# Sheet1.net
KiCad netlist of a schematic drawn in Altium Designer
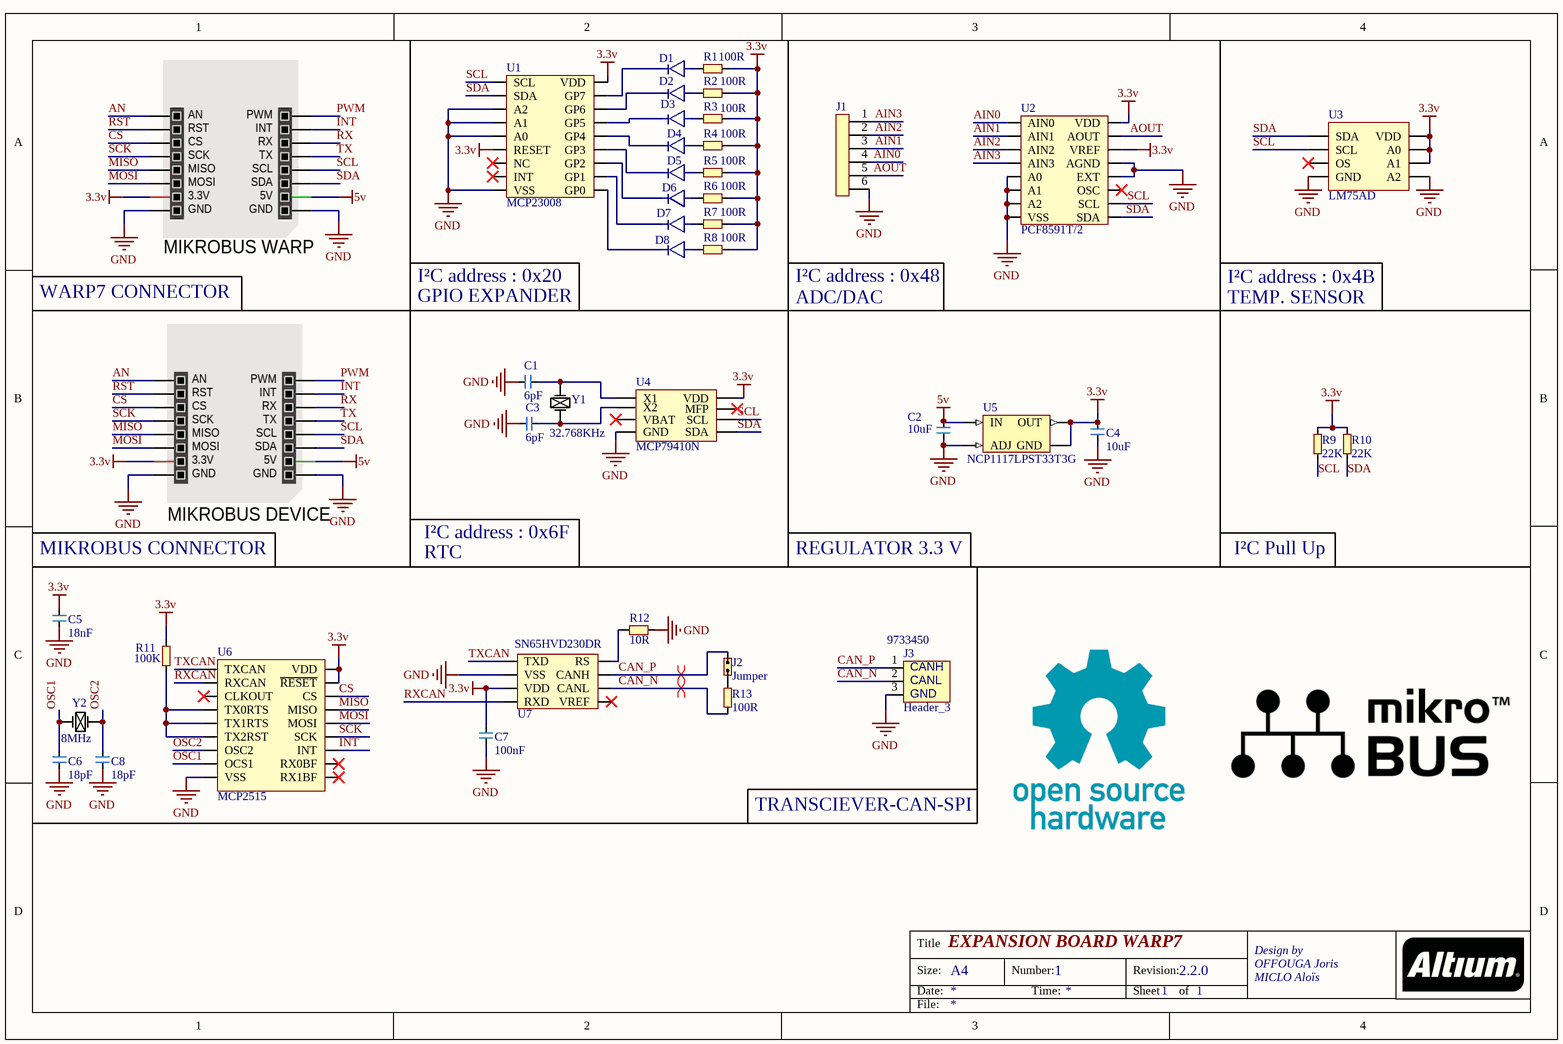
[diagram p0: Sheet1.SchDoc]

(export (version "E")
  (design (tool "Eeschema 10.0.6"))
  (components
    (comp (ref "C1")
      (value "6pF")
      (footprint "0805")
      (description "Condensateur")
      (libsource (lib "Schlib1") (part "Condensateur"))
    )
    (comp (ref "C2")
      (value "10uF")
      (footprint "0805")
      (description "Condensateur")
      (libsource (lib "Schlib1") (part "Condensateur"))
    )
    (comp (ref "C3")
      (value "6pF")
      (footprint "0805")
      (description "Condensateur")
      (libsource (lib "Schlib1") (part "Condensateur"))
    )
    (comp (ref "C4")
      (value "10uF")
      (footprint "0805")
      (description "Condensateur")
      (libsource (lib "Schlib1") (part "Condensateur"))
    )
    (comp (ref "C5")
      (value "18nF")
      (footprint "0805")
      (description "Condensateur")
      (libsource (lib "Schlib1") (part "Condensateur"))
    )
    (comp (ref "C6")
      (value "18pF")
      (footprint "0805")
      (description "Condensateur")
      (libsource (lib "Schlib1") (part "Condensateur"))
    )
    (comp (ref "C7")
      (value "100nF")
      (footprint "0805")
      (description "Condensateur")
      (libsource (lib "Schlib1") (part "Condensateur"))
    )
    (comp (ref "C8")
      (value "18pF")
      (footprint "0805")
      (description "Condensateur")
      (libsource (lib "Schlib1") (part "Condensateur"))
    )
    (comp (ref "D1")
      (value "Diode")
      (footprint "led")
      (description "led")
      (libsource (lib "Schlib1") (part "Diode"))
    )
    (comp (ref "D2")
      (value "Diode")
      (footprint "led")
      (description "led")
      (libsource (lib "Schlib1") (part "Diode"))
    )
    (comp (ref "D3")
      (value "Diode")
      (footprint "led")
      (description "led")
      (libsource (lib "Schlib1") (part "Diode"))
    )
    (comp (ref "D4")
      (value "Diode")
      (footprint "led")
      (description "led")
      (libsource (lib "Schlib1") (part "Diode"))
    )
    (comp (ref "D5")
      (value "Diode")
      (footprint "led")
      (description "led")
      (libsource (lib "Schlib1") (part "Diode"))
    )
    (comp (ref "D6")
      (value "Diode")
      (footprint "led")
      (description "led")
      (libsource (lib "Schlib1") (part "Diode"))
    )
    (comp (ref "D7")
      (value "Diode")
      (footprint "led")
      (description "led")
      (libsource (lib "Schlib1") (part "Diode"))
    )
    (comp (ref "D8")
      (value "Diode")
      (footprint "led")
      (description "led")
      (libsource (lib "Schlib1") (part "Diode"))
    )
    (comp (ref "J1") (value "Header_6") (footprint "Header 6") (libsource (lib "Schlib1") (part "Header_6")))
    (comp (ref "J2") (value "Jumper") (footprint "Header 2") (libsource (lib "Schlib1") (part "Jumper")))
    (comp (ref "J3")
      (value "Header_3")
      (footprint "Header 3")
      (fields (field (name "SUPPLIER PART NUMBER 1") "9733450"))
      (libsource (lib "Schlib1") (part "Header_3"))
    )
    (comp (ref "MIKROBUS DEVICE")
      (value "MIKROBUS HOST CONN.")
      (footprint "MIKROBUS HOST CONN.")
      (description "mikroBUS Host Socket")
      (libsource (lib "altium-import") (part "root_0_MIKROBUS HOST CONN._1_"))
    )
    (comp (ref "MIKROBUS WARP")
      (value "MIKROBUS HOST CONN.")
      (footprint "MIKROBUS WARP CONN.")
      (description "mikroBUS Host Socket")
      (libsource (lib "altium-import") (part "root_0_MIKROBUS HOST CONN._1_"))
    )
    (comp (ref "R1") (value "100R") (footprint "0805") (libsource (lib "") (part "Resistance_1")))
    (comp (ref "R2") (value "100R") (footprint "0805") (libsource (lib "") (part "Resistance_1")))
    (comp (ref "R3") (value "100R") (footprint "0805") (libsource (lib "") (part "Resistance_1")))
    (comp (ref "R4") (value "100R") (footprint "0805") (libsource (lib "") (part "Resistance_1")))
    (comp (ref "R5") (value "100R") (footprint "0805") (libsource (lib "") (part "Resistance_1")))
    (comp (ref "R6") (value "100R") (footprint "0805") (libsource (lib "") (part "Resistance_1")))
    (comp (ref "R7") (value "100R") (footprint "0805") (libsource (lib "") (part "Resistance_1")))
    (comp (ref "R8") (value "100R") (footprint "0805") (libsource (lib "") (part "Resistance_1")))
    (comp (ref "R9") (value "22K") (footprint "0805") (libsource (lib "Schlib1") (part "Resistance")))
    (comp (ref "R10") (value "22K") (footprint "0805") (libsource (lib "Schlib1") (part "Resistance")))
    (comp (ref "R11") (value "100K") (footprint "0805") (libsource (lib "Schlib1") (part "Resistance")))
    (comp (ref "R12") (value "10R") (footprint "0805") (libsource (lib "") (part "Resistance_2")))
    (comp (ref "R13") (value "100R") (footprint "0805") (libsource (lib "Schlib1") (part "Resistance")))
    (comp (ref "U1") (value "MCP23008") (footprint "SOIC 18") (libsource (lib "Schlib1") (part "MCP23008")))
    (comp (ref "U2")
      (value "PCF8591T/2")
      (footprint "SOIC 16")
      (libsource (lib "Schlib1") (part "PCF8591T/2"))
    )
    (comp (ref "U3") (value "LM75AD") (footprint "SOIC 8") (libsource (lib "Schlib1") (part "LM75AD")))
    (comp (ref "U4") (value "MCP79410N") (footprint "SOIC 8") (libsource (lib "Schlib1") (part "MCP7940N")))
    (comp (ref "U5")
      (value "NCP1117LPST33T3G")
      (footprint "SOT-223")
      (libsource (lib "Schlib1") (part "NCP1117LPST33T3G"))
    )
    (comp (ref "U6") (value "MCP2515") (footprint "SOIC 18") (libsource (lib "Schlib1") (part "MCP2515")))
    (comp (ref "U7")
      (value "SN65HVD230DR")
      (footprint "SOIC 8")
      (libsource (lib "altium-import") (part "root_0_SN65HVD230DR_"))
    )
    (comp (ref "Y1") (value "32.768KHz") (footprint "ABS-07") (libsource (lib "") (part "Quartz_1")))
    (comp (ref "Y2")
      (value "8MHz")
      (footprint "QUARTZ_CMS_6.2x3.7")
      (libsource (lib "Schlib1") (part "Quartz"))
    )
  )
  (nets
    (net (code "1") (name "/AIN0") (class "Default")
      (node (ref "J1") (pin "4") (pinfunction "4_4") (pintype "passive"))
      (node (ref "U2") (pin "1") (pinfunction "AIN0_1") (pintype "passive"))
    )
    (net (code "2") (name "/AIN1") (class "Default")
      (node (ref "J1") (pin "3") (pinfunction "3_3") (pintype "passive"))
      (node (ref "U2") (pin "2") (pinfunction "AIN1_2") (pintype "passive"))
    )
    (net (code "3") (name "/AIN2") (class "Default")
      (node (ref "J1") (pin "2") (pinfunction "2_2") (pintype "passive"))
      (node (ref "U2") (pin "3") (pinfunction "AIN2_3") (pintype "passive"))
    )
    (net (code "4") (name "/AIN3") (class "Default")
      (node (ref "J1") (pin "1") (pinfunction "1_1") (pintype "passive"))
      (node (ref "U2") (pin "4") (pinfunction "AIN3_4") (pintype "passive"))
    )
    (net (code "5") (name "/AN") (class "Default")
      (node (ref "MIKROBUS DEVICE") (pin "1") (pinfunction "AN_1") (pintype "passive"))
      (node (ref "MIKROBUS WARP") (pin "1") (pinfunction "AN_1") (pintype "passive"))
    )
    (net (code "6") (name "/AOUT") (class "Default")
      (node (ref "J1") (pin "5") (pinfunction "5_5") (pintype "passive"))
      (node (ref "U2") (pin "15") (pinfunction "AOUT_15") (pintype "passive"))
    )
    (net (code "7") (name "/CAN_N") (class "Default")
      (node (ref "J3") (pin "2") (pinfunction "2_2") (pintype "passive"))
      (node (ref "R13") (pin "1") (pinfunction "1_1") (pintype "passive"))
      (node (ref "U7") (pin "6") (pinfunction "CANL_6") (pintype "passive"))
    )
    (net (code "8") (name "/CAN_P") (class "Default")
      (node (ref "J2") (pin "1") (pinfunction "1_1") (pintype "passive"))
      (node (ref "J3") (pin "1") (pinfunction "1_1") (pintype "passive"))
      (node (ref "U7") (pin "7") (pinfunction "CANH_7") (pintype "passive"))
    )
    (net (code "9") (name "/CS") (class "Default")
      (node (ref "MIKROBUS DEVICE") (pin "3") (pinfunction "CS_3") (pintype "passive"))
      (node (ref "MIKROBUS WARP") (pin "3") (pinfunction "CS_3") (pintype "passive"))
      (node (ref "U6") (pin "16") (pinfunction "CS_16") (pintype "passive"))
    )
    (net (code "10") (name "/INT") (class "Default")
      (node (ref "MIKROBUS DEVICE") (pin "15") (pinfunction "INT_15") (pintype "passive"))
      (node (ref "MIKROBUS WARP") (pin "15") (pinfunction "INT_15") (pintype "passive"))
      (node (ref "U6") (pin "12") (pinfunction "INT_12") (pintype "passive"))
    )
    (net (code "11") (name "/MISO") (class "Default")
      (node (ref "MIKROBUS DEVICE") (pin "5") (pinfunction "MISO_5") (pintype "passive"))
      (node (ref "MIKROBUS WARP") (pin "5") (pinfunction "MISO_5") (pintype "passive"))
      (node (ref "U6") (pin "15") (pinfunction "MISO_15") (pintype "passive"))
    )
    (net (code "12") (name "/MOSI") (class "Default")
      (node (ref "MIKROBUS DEVICE") (pin "6") (pinfunction "MOSI_6") (pintype "passive"))
      (node (ref "MIKROBUS WARP") (pin "6") (pinfunction "MOSI_6") (pintype "passive"))
      (node (ref "U6") (pin "14") (pinfunction "MOSI_14") (pintype "passive"))
    )
    (net (code "13") (name "/OSC1") (class "Default")
      (node (ref "C6") (pin "2") (pinfunction "2_2") (pintype "passive"))
      (node (ref "U6") (pin "8") (pinfunction "OCS1_8") (pintype "passive"))
      (node (ref "Y2") (pin "1") (pinfunction "1_1") (pintype "passive"))
    )
    (net (code "14") (name "/OSC2") (class "Default")
      (node (ref "C8") (pin "2") (pinfunction "2_2") (pintype "passive"))
      (node (ref "U6") (pin "7") (pinfunction "OSC2_7") (pintype "passive"))
      (node (ref "Y2") (pin "2") (pinfunction "2_2") (pintype "passive"))
    )
    (net (code "15") (name "/PWM") (class "Default")
      (node (ref "MIKROBUS DEVICE") (pin "16") (pinfunction "PWM_16") (pintype "passive"))
      (node (ref "MIKROBUS WARP") (pin "16") (pinfunction "PWM_16") (pintype "passive"))
    )
    (net (code "16") (name "/RST") (class "Default")
      (node (ref "MIKROBUS DEVICE") (pin "2") (pinfunction "RST_2") (pintype "passive"))
      (node (ref "MIKROBUS WARP") (pin "2") (pinfunction "RST_2") (pintype "passive"))
    )
    (net (code "17") (name "/RX") (class "Default")
      (node (ref "MIKROBUS DEVICE") (pin "14") (pinfunction "RX_14") (pintype "passive"))
      (node (ref "MIKROBUS WARP") (pin "14") (pinfunction "RX_14") (pintype "passive"))
    )
    (net (code "18") (name "/RXCAN") (class "Default")
      (node (ref "U6") (pin "2") (pinfunction "RXCAN_2") (pintype "passive"))
      (node (ref "U7") (pin "4") (pinfunction "RXD_4") (pintype "passive"))
    )
    (net (code "19") (name "/SCK") (class "Default")
      (node (ref "MIKROBUS DEVICE") (pin "4") (pinfunction "SCK_4") (pintype "passive"))
      (node (ref "MIKROBUS WARP") (pin "4") (pinfunction "SCK_4") (pintype "passive"))
      (node (ref "U6") (pin "13") (pinfunction "SCK_13") (pintype "passive"))
    )
    (net (code "20") (name "/SCL") (class "Default")
      (node (ref "MIKROBUS DEVICE") (pin "12") (pinfunction "SCL_12") (pintype "passive"))
      (node (ref "MIKROBUS WARP") (pin "12") (pinfunction "SCL_12") (pintype "passive"))
      (node (ref "R9") (pin "1") (pinfunction "1_1") (pintype "passive"))
      (node (ref "U1") (pin "1") (pinfunction "SCL_1") (pintype "passive"))
      (node (ref "U2") (pin "10") (pinfunction "SCL_10") (pintype "passive"))
      (node (ref "U3") (pin "2") (pinfunction "SCL_2") (pintype "passive"))
      (node (ref "U4") (pin "6") (pinfunction "SCL_6") (pintype "passive"))
    )
    (net (code "21") (name "/SDA") (class "Default")
      (node (ref "MIKROBUS DEVICE") (pin "11") (pinfunction "SDA_11") (pintype "passive"))
      (node (ref "MIKROBUS WARP") (pin "11") (pinfunction "SDA_11") (pintype "passive"))
      (node (ref "R10") (pin "1") (pinfunction "1_1") (pintype "passive"))
      (node (ref "U1") (pin "2") (pinfunction "SDA_2") (pintype "passive"))
      (node (ref "U2") (pin "9") (pinfunction "SDA_9") (pintype "passive"))
      (node (ref "U3") (pin "1") (pinfunction "SDA_1") (pintype "passive"))
      (node (ref "U4") (pin "5") (pinfunction "SDA_5") (pintype "passive"))
    )
    (net (code "22") (name "/TX") (class "Default")
      (node (ref "MIKROBUS DEVICE") (pin "13") (pinfunction "TX_13") (pintype "passive"))
      (node (ref "MIKROBUS WARP") (pin "13") (pinfunction "TX_13") (pintype "passive"))
    )
    (net (code "23") (name "/TXCAN") (class "Default")
      (node (ref "U6") (pin "1") (pinfunction "TXCAN_1") (pintype "passive"))
      (node (ref "U7") (pin "1") (pinfunction "TXD_1") (pintype "passive"))
    )
    (net (code "24") (name "3.3v") (class "Default")
      (node (ref "C4") (pin "1") (pinfunction "1_1") (pintype "passive"))
      (node (ref "C5") (pin "1") (pinfunction "1_1") (pintype "passive"))
      (node (ref "C7") (pin "2") (pinfunction "2_2") (pintype "passive"))
      (node (ref "MIKROBUS DEVICE") (pin "7") (pinfunction "3.3V_7") (pintype "passive"))
      (node (ref "MIKROBUS WARP") (pin "7") (pinfunction "3.3V_7") (pintype "passive"))
      (node (ref "R1") (pin "2") (pinfunction "2_2") (pintype "passive"))
      (node (ref "R10") (pin "2") (pinfunction "2_2") (pintype "passive"))
      (node (ref "R11") (pin "2") (pinfunction "2_2") (pintype "passive"))
      (node (ref "R2") (pin "2") (pinfunction "2_2") (pintype "passive"))
      (node (ref "R3") (pin "2") (pinfunction "2_2") (pintype "passive"))
      (node (ref "R4") (pin "2") (pinfunction "2_2") (pintype "passive"))
      (node (ref "R5") (pin "2") (pinfunction "2_2") (pintype "passive"))
      (node (ref "R6") (pin "2") (pinfunction "2_2") (pintype "passive"))
      (node (ref "R7") (pin "2") (pinfunction "2_2") (pintype "passive"))
      (node (ref "R8") (pin "2") (pinfunction "2_2") (pintype "passive"))
      (node (ref "R9") (pin "2") (pinfunction "2_2") (pintype "passive"))
      (node (ref "U1") (pin "18") (pinfunction "VDD_18") (pintype "passive"))
      (node (ref "U1") (pin "6") (pinfunction "RESET_6") (pintype "passive"))
      (node (ref "U2") (pin "14") (pinfunction "VREF_14") (pintype "passive"))
      (node (ref "U2") (pin "16") (pinfunction "VDD_16") (pintype "passive"))
      (node (ref "U3") (pin "6") (pinfunction "A1_6") (pintype "passive"))
      (node (ref "U3") (pin "7") (pinfunction "A0_7") (pintype "passive"))
      (node (ref "U3") (pin "8") (pinfunction "VDD_8") (pintype "passive"))
      (node (ref "U4") (pin "8") (pinfunction "VDD_8") (pintype "passive"))
      (node (ref "U5") (pin "2") (pinfunction "OUT_2") (pintype "output"))
      (node (ref "U5") (pin "4") (pinfunction "GND_4") (pintype "passive"))
      (node (ref "U6") (pin "17") (pinfunction "~{RESET}_17") (pintype "passive"))
      (node (ref "U6") (pin "18") (pinfunction "VDD_18") (pintype "passive"))
      (node (ref "U7") (pin "3") (pinfunction "VDD_3") (pintype "passive"))
    )
    (net (code "25") (name "5v") (class "Default")
      (node (ref "C2") (pin "1") (pinfunction "1_1") (pintype "passive"))
      (node (ref "MIKROBUS DEVICE") (pin "10") (pinfunction "5V_10") (pintype "passive"))
      (node (ref "MIKROBUS WARP") (pin "10") (pinfunction "5V_10") (pintype "passive"))
      (node (ref "U5") (pin "3") (pinfunction "IN_3") (pintype "input"))
    )
    (net (code "26") (name "GND") (class "Default")
      (node (ref "C1") (pin "2") (pinfunction "2_2") (pintype "passive"))
      (node (ref "C2") (pin "2") (pinfunction "2_2") (pintype "passive"))
      (node (ref "C3") (pin "2") (pinfunction "2_2") (pintype "passive"))
      (node (ref "C4") (pin "2") (pinfunction "2_2") (pintype "passive"))
      (node (ref "C5") (pin "2") (pinfunction "2_2") (pintype "passive"))
      (node (ref "C6") (pin "1") (pinfunction "1_1") (pintype "passive"))
      (node (ref "C7") (pin "1") (pinfunction "1_1") (pintype "passive"))
      (node (ref "C8") (pin "1") (pinfunction "1_1") (pintype "passive"))
      (node (ref "J1") (pin "6") (pinfunction "6_6") (pintype "passive"))
      (node (ref "J3") (pin "3") (pinfunction "3_3") (pintype "passive"))
      (node (ref "MIKROBUS DEVICE") (pin "8") (pinfunction "GND_8") (pintype "passive"))
      (node (ref "MIKROBUS DEVICE") (pin "9") (pinfunction "GND_9") (pintype "passive"))
      (node (ref "MIKROBUS WARP") (pin "8") (pinfunction "GND_8") (pintype "passive"))
      (node (ref "MIKROBUS WARP") (pin "9") (pinfunction "GND_9") (pintype "passive"))
      (node (ref "R12") (pin "1") (pinfunction "1_1") (pintype "passive"))
      (node (ref "U1") (pin "3") (pinfunction "A2_3") (pintype "passive"))
      (node (ref "U1") (pin "4") (pinfunction "A1_4") (pintype "passive"))
      (node (ref "U1") (pin "5") (pinfunction "A0_5") (pintype "passive"))
      (node (ref "U1") (pin "9") (pinfunction "VSS_9") (pintype "passive"))
      (node (ref "U2") (pin "12") (pinfunction "EXT_12") (pintype "passive"))
      (node (ref "U2") (pin "13") (pinfunction "AGND_13") (pintype "passive"))
      (node (ref "U2") (pin "5") (pinfunction "A0_5") (pintype "passive"))
      (node (ref "U2") (pin "6") (pinfunction "A1_6") (pintype "passive"))
      (node (ref "U2") (pin "7") (pinfunction "A2_7") (pintype "passive"))
      (node (ref "U2") (pin "8") (pinfunction "VSS_8") (pintype "passive"))
      (node (ref "U3") (pin "4") (pinfunction "GND_4") (pintype "passive"))
      (node (ref "U3") (pin "5") (pinfunction "A2_5") (pintype "passive"))
      (node (ref "U4") (pin "4") (pinfunction "GND_4") (pintype "passive"))
      (node (ref "U5") (pin "1") (pinfunction "ADJ_1") (pintype "input"))
      (node (ref "U6") (pin "9") (pinfunction "VSS_9") (pintype "passive"))
      (node (ref "U7") (pin "2") (pinfunction "VSS_2") (pintype "passive"))
    )
    (net (code "27") (name "Net-(D1-Pad1)") (class "Default")
      (node (ref "D1") (pin "1") (pinfunction "1_1") (pintype "passive"))
      (node (ref "R1") (pin "1") (pinfunction "1_1") (pintype "passive"))
    )
    (net (code "28") (name "Net-(D2-Pad1)") (class "Default")
      (node (ref "D2") (pin "1") (pinfunction "1_1") (pintype "passive"))
      (node (ref "R2") (pin "1") (pinfunction "1_1") (pintype "passive"))
    )
    (net (code "29") (name "Net-(D3-Pad1)") (class "Default")
      (node (ref "D3") (pin "1") (pinfunction "1_1") (pintype "passive"))
      (node (ref "R3") (pin "1") (pinfunction "1_1") (pintype "passive"))
    )
    (net (code "30") (name "Net-(D4-Pad1)") (class "Default")
      (node (ref "D4") (pin "1") (pinfunction "1_1") (pintype "passive"))
      (node (ref "R4") (pin "1") (pinfunction "1_1") (pintype "passive"))
    )
    (net (code "31") (name "Net-(D5-Pad1)") (class "Default")
      (node (ref "D5") (pin "1") (pinfunction "1_1") (pintype "passive"))
      (node (ref "R5") (pin "1") (pinfunction "1_1") (pintype "passive"))
    )
    (net (code "32") (name "Net-(D6-Pad1)") (class "Default")
      (node (ref "D6") (pin "1") (pinfunction "1_1") (pintype "passive"))
      (node (ref "R6") (pin "1") (pinfunction "1_1") (pintype "passive"))
    )
    (net (code "33") (name "Net-(D7-Pad1)") (class "Default")
      (node (ref "D7") (pin "1") (pinfunction "1_1") (pintype "passive"))
      (node (ref "R7") (pin "1") (pinfunction "1_1") (pintype "passive"))
    )
    (net (code "34") (name "Net-(D8-Pad1)") (class "Default")
      (node (ref "D8") (pin "1") (pinfunction "1_1") (pintype "passive"))
      (node (ref "R8") (pin "1") (pinfunction "1_1") (pintype "passive"))
    )
    (net (code "35") (name "Net-(J2-Pad2)") (class "Default")
      (node (ref "J2") (pin "2") (pinfunction "2_2") (pintype "passive"))
      (node (ref "R13") (pin "2") (pinfunction "2_2") (pintype "passive"))
    )
    (net (code "36") (name "Net-(U1-GP0)") (class "Default")
      (node (ref "D8") (pin "2") (pinfunction "2_2") (pintype "passive"))
      (node (ref "U1") (pin "10") (pinfunction "GP0_10") (pintype "passive"))
    )
    (net (code "37") (name "Net-(U1-GP1)") (class "Default")
      (node (ref "D7") (pin "2") (pinfunction "2_2") (pintype "passive"))
      (node (ref "U1") (pin "11") (pinfunction "GP1_11") (pintype "passive"))
    )
    (net (code "38") (name "Net-(U1-GP2)") (class "Default")
      (node (ref "D6") (pin "2") (pinfunction "2_2") (pintype "passive"))
      (node (ref "U1") (pin "12") (pinfunction "GP2_12") (pintype "passive"))
    )
    (net (code "39") (name "Net-(U1-GP3)") (class "Default")
      (node (ref "D5") (pin "2") (pinfunction "2_2") (pintype "passive"))
      (node (ref "U1") (pin "13") (pinfunction "GP3_13") (pintype "passive"))
    )
    (net (code "40") (name "Net-(U1-GP4)") (class "Default")
      (node (ref "D4") (pin "2") (pinfunction "2_2") (pintype "passive"))
      (node (ref "U1") (pin "14") (pinfunction "GP4_14") (pintype "passive"))
    )
    (net (code "41") (name "Net-(U1-GP5)") (class "Default")
      (node (ref "D3") (pin "2") (pinfunction "2_2") (pintype "passive"))
      (node (ref "U1") (pin "15") (pinfunction "GP5_15") (pintype "passive"))
    )
    (net (code "42") (name "Net-(U1-GP6)") (class "Default")
      (node (ref "D2") (pin "2") (pinfunction "2_2") (pintype "passive"))
      (node (ref "U1") (pin "16") (pinfunction "GP6_16") (pintype "passive"))
    )
    (net (code "43") (name "Net-(U1-GP7)") (class "Default")
      (node (ref "D1") (pin "2") (pinfunction "2_2") (pintype "passive"))
      (node (ref "U1") (pin "17") (pinfunction "GP7_17") (pintype "passive"))
    )
    (net (code "44") (name "Net-(U4-X1)") (class "Default")
      (node (ref "C1") (pin "1") (pinfunction "1_1") (pintype "passive"))
      (node (ref "U4") (pin "1") (pinfunction "X1_1") (pintype "passive"))
      (node (ref "Y1") (pin "1") (pinfunction "1_1") (pintype "passive"))
    )
    (net (code "45") (name "Net-(U4-X2)") (class "Default")
      (node (ref "C3") (pin "1") (pinfunction "1_1") (pintype "passive"))
      (node (ref "U4") (pin "2") (pinfunction "X2_2") (pintype "passive"))
      (node (ref "Y1") (pin "2") (pinfunction "2_2") (pintype "passive"))
    )
    (net (code "46") (name "Net-(U6-TX0RTS)") (class "Default")
      (node (ref "R11") (pin "1") (pinfunction "1_1") (pintype "passive"))
      (node (ref "U6") (pin "4") (pinfunction "TX0RTS_4") (pintype "passive"))
      (node (ref "U6") (pin "5") (pinfunction "TX1RTS_5") (pintype "passive"))
      (node (ref "U6") (pin "6") (pinfunction "TX2RST_6") (pintype "passive"))
    )
    (net (code "47") (name "Net-(U7-RS)") (class "Default")
      (node (ref "R12") (pin "2") (pinfunction "2_2") (pintype "passive"))
      (node (ref "U7") (pin "8") (pinfunction "RS_8") (pintype "passive"))
    )
    (net (code "48") (name "unconnected-(U1-INT-Pad8)") (class "Default")
      (node (ref "U1") (pin "8") (pinfunction "INT_8") (pintype "passive+no_connect"))
    )
    (net (code "49") (name "unconnected-(U1-NC-Pad7)") (class "Default")
      (node (ref "U1") (pin "7") (pinfunction "NC_7") (pintype "passive+no_connect"))
    )
    (net (code "50") (name "unconnected-(U2-OSC-Pad11)") (class "Default")
      (node (ref "U2") (pin "11") (pinfunction "OSC_11") (pintype "passive+no_connect"))
    )
    (net (code "51") (name "unconnected-(U3-OS-Pad3)") (class "Default")
      (node (ref "U3") (pin "3") (pinfunction "OS_3") (pintype "passive+no_connect"))
    )
    (net (code "52") (name "unconnected-(U4-MFP-Pad7)") (class "Default")
      (node (ref "U4") (pin "7") (pinfunction "MFP_7") (pintype "passive+no_connect"))
    )
    (net (code "53") (name "unconnected-(U4-VBAT-Pad3)") (class "Default")
      (node (ref "U4") (pin "3") (pinfunction "VBAT_3") (pintype "passive+no_connect"))
    )
    (net (code "54") (name "unconnected-(U6-CLKOUT-Pad3)") (class "Default")
      (node (ref "U6") (pin "3") (pinfunction "CLKOUT_3") (pintype "passive+no_connect"))
    )
    (net (code "55") (name "unconnected-(U6-RX0BF-Pad11)") (class "Default")
      (node (ref "U6") (pin "11") (pinfunction "RX0BF_11") (pintype "passive+no_connect"))
    )
    (net (code "56") (name "unconnected-(U6-RX1BF-Pad10)") (class "Default")
      (node (ref "U6") (pin "10") (pinfunction "RX1BF_10") (pintype "passive+no_connect"))
    )
    (net (code "57") (name "unconnected-(U7-VREF-Pad5)") (class "Default")
      (node (ref "U7") (pin "5") (pinfunction "VREF_5") (pintype "passive+no_connect"))
    )
  )
)
